# analog_sensor_x8.net
KiCad netlist of a schematic drawn in EAGLE
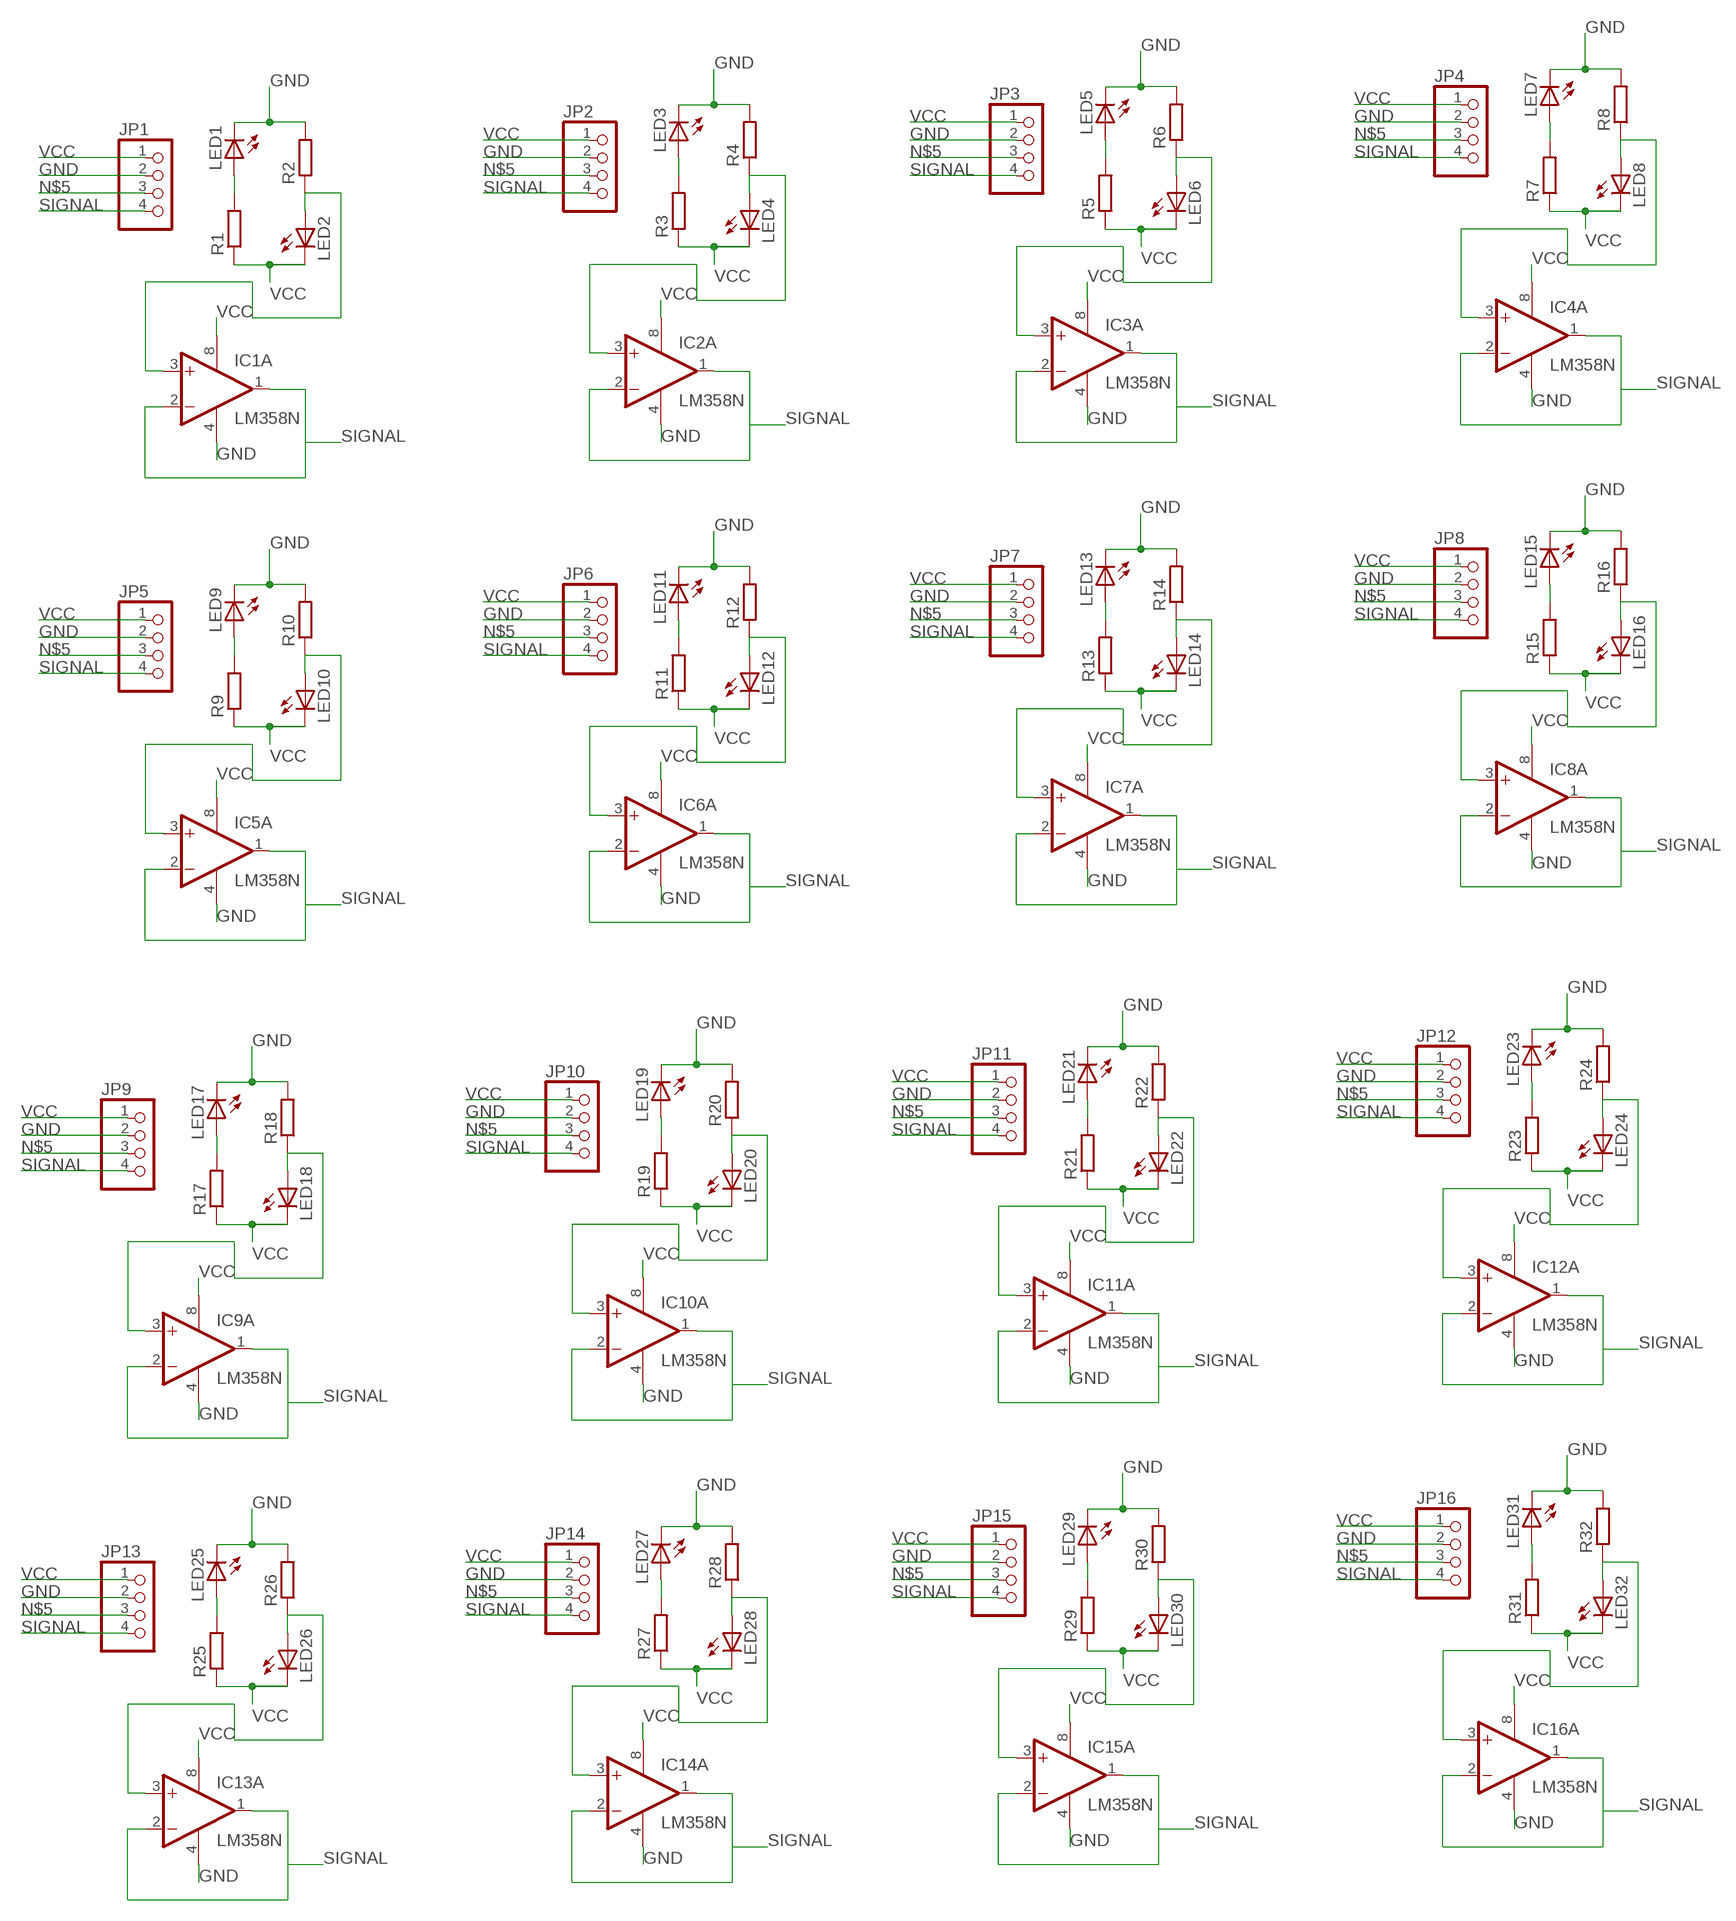
[diagram p0: schematic, sheet 1]

(export (version "E")
  (design (tool "Eeschema 10.0.6"))
  (components
    (comp (ref "IC1")
      (value "LM358N")
      (footprint "eagle-import:DIL08")
      (libsource (lib "eagle-import") (part "LM358N"))
    )
    (comp (ref "IC2")
      (value "LM358N")
      (footprint "eagle-import:DIL08")
      (libsource (lib "eagle-import") (part "LM358N"))
    )
    (comp (ref "IC3")
      (value "LM358N")
      (footprint "eagle-import:DIL08")
      (libsource (lib "eagle-import") (part "LM358N"))
    )
    (comp (ref "IC4")
      (value "LM358N")
      (footprint "eagle-import:DIL08")
      (libsource (lib "eagle-import") (part "LM358N"))
    )
    (comp (ref "IC5")
      (value "LM358N")
      (footprint "eagle-import:DIL08")
      (libsource (lib "eagle-import") (part "LM358N"))
    )
    (comp (ref "IC6")
      (value "LM358N")
      (footprint "eagle-import:DIL08")
      (libsource (lib "eagle-import") (part "LM358N"))
    )
    (comp (ref "IC7")
      (value "LM358N")
      (footprint "eagle-import:DIL08")
      (libsource (lib "eagle-import") (part "LM358N"))
    )
    (comp (ref "IC8")
      (value "LM358N")
      (footprint "eagle-import:DIL08")
      (libsource (lib "eagle-import") (part "LM358N"))
    )
    (comp (ref "IC9")
      (value "LM358N")
      (footprint "eagle-import:DIL08")
      (libsource (lib "eagle-import") (part "LM358N"))
    )
    (comp (ref "IC10")
      (value "LM358N")
      (footprint "eagle-import:DIL08")
      (libsource (lib "eagle-import") (part "LM358N"))
    )
    (comp (ref "IC11")
      (value "LM358N")
      (footprint "eagle-import:DIL08")
      (libsource (lib "eagle-import") (part "LM358N"))
    )
    (comp (ref "IC12")
      (value "LM358N")
      (footprint "eagle-import:DIL08")
      (libsource (lib "eagle-import") (part "LM358N"))
    )
    (comp (ref "IC13")
      (value "LM358N")
      (footprint "eagle-import:DIL08")
      (libsource (lib "eagle-import") (part "LM358N"))
    )
    (comp (ref "IC14")
      (value "LM358N")
      (footprint "eagle-import:DIL08")
      (libsource (lib "eagle-import") (part "LM358N"))
    )
    (comp (ref "IC15")
      (value "LM358N")
      (footprint "eagle-import:DIL08")
      (libsource (lib "eagle-import") (part "LM358N"))
    )
    (comp (ref "IC16")
      (value "LM358N")
      (footprint "eagle-import:DIL08")
      (libsource (lib "eagle-import") (part "LM358N"))
    )
    (comp (ref "JP1")
      (value "PINHD-1X4")
      (footprint "eagle-import:1X04")
      (libsource (lib "eagle-import") (part "PINHD-1X4"))
    )
    (comp (ref "JP2")
      (value "PINHD-1X4")
      (footprint "eagle-import:1X04")
      (libsource (lib "eagle-import") (part "PINHD-1X4"))
    )
    (comp (ref "JP3")
      (value "PINHD-1X4")
      (footprint "eagle-import:1X04")
      (libsource (lib "eagle-import") (part "PINHD-1X4"))
    )
    (comp (ref "JP4")
      (value "PINHD-1X4")
      (footprint "eagle-import:1X04")
      (libsource (lib "eagle-import") (part "PINHD-1X4"))
    )
    (comp (ref "JP5")
      (value "PINHD-1X4")
      (footprint "eagle-import:1X04")
      (libsource (lib "eagle-import") (part "PINHD-1X4"))
    )
    (comp (ref "JP6")
      (value "PINHD-1X4")
      (footprint "eagle-import:1X04")
      (libsource (lib "eagle-import") (part "PINHD-1X4"))
    )
    (comp (ref "JP7")
      (value "PINHD-1X4")
      (footprint "eagle-import:1X04")
      (libsource (lib "eagle-import") (part "PINHD-1X4"))
    )
    (comp (ref "JP8")
      (value "PINHD-1X4")
      (footprint "eagle-import:1X04")
      (libsource (lib "eagle-import") (part "PINHD-1X4"))
    )
    (comp (ref "JP9")
      (value "PINHD-1X4")
      (footprint "eagle-import:1X04")
      (libsource (lib "eagle-import") (part "PINHD-1X4"))
    )
    (comp (ref "JP10")
      (value "PINHD-1X4")
      (footprint "eagle-import:1X04")
      (libsource (lib "eagle-import") (part "PINHD-1X4"))
    )
    (comp (ref "JP11")
      (value "PINHD-1X4")
      (footprint "eagle-import:1X04")
      (libsource (lib "eagle-import") (part "PINHD-1X4"))
    )
    (comp (ref "JP12")
      (value "PINHD-1X4")
      (footprint "eagle-import:1X04")
      (libsource (lib "eagle-import") (part "PINHD-1X4"))
    )
    (comp (ref "JP13")
      (value "PINHD-1X4")
      (footprint "eagle-import:1X04")
      (libsource (lib "eagle-import") (part "PINHD-1X4"))
    )
    (comp (ref "JP14")
      (value "PINHD-1X4")
      (footprint "eagle-import:1X04")
      (libsource (lib "eagle-import") (part "PINHD-1X4"))
    )
    (comp (ref "JP15")
      (value "PINHD-1X4")
      (footprint "eagle-import:1X04")
      (libsource (lib "eagle-import") (part "PINHD-1X4"))
    )
    (comp (ref "JP16")
      (value "PINHD-1X4")
      (footprint "eagle-import:1X04")
      (libsource (lib "eagle-import") (part "PINHD-1X4"))
    )
    (comp (ref "LED1")
      (value "LED5MM")
      (footprint "eagle-import:LED5MM")
      (libsource (lib "eagle-import") (part "LED5MM"))
    )
    (comp (ref "LED2")
      (value "LED5MM")
      (footprint "eagle-import:LED5MM")
      (libsource (lib "eagle-import") (part "LED5MM"))
    )
    (comp (ref "LED3")
      (value "LED5MM")
      (footprint "eagle-import:LED5MM")
      (libsource (lib "eagle-import") (part "LED5MM"))
    )
    (comp (ref "LED4")
      (value "LED5MM")
      (footprint "eagle-import:LED5MM")
      (libsource (lib "eagle-import") (part "LED5MM"))
    )
    (comp (ref "LED5")
      (value "LED5MM")
      (footprint "eagle-import:LED5MM")
      (libsource (lib "eagle-import") (part "LED5MM"))
    )
    (comp (ref "LED6")
      (value "LED5MM")
      (footprint "eagle-import:LED5MM")
      (libsource (lib "eagle-import") (part "LED5MM"))
    )
    (comp (ref "LED7")
      (value "LED5MM")
      (footprint "eagle-import:LED5MM")
      (libsource (lib "eagle-import") (part "LED5MM"))
    )
    (comp (ref "LED8")
      (value "LED5MM")
      (footprint "eagle-import:LED5MM")
      (libsource (lib "eagle-import") (part "LED5MM"))
    )
    (comp (ref "LED9")
      (value "LED5MM")
      (footprint "eagle-import:LED5MM")
      (libsource (lib "eagle-import") (part "LED5MM"))
    )
    (comp (ref "LED10")
      (value "LED5MM")
      (footprint "eagle-import:LED5MM")
      (libsource (lib "eagle-import") (part "LED5MM"))
    )
    (comp (ref "LED11")
      (value "LED5MM")
      (footprint "eagle-import:LED5MM")
      (libsource (lib "eagle-import") (part "LED5MM"))
    )
    (comp (ref "LED12")
      (value "LED5MM")
      (footprint "eagle-import:LED5MM")
      (libsource (lib "eagle-import") (part "LED5MM"))
    )
    (comp (ref "LED13")
      (value "LED5MM")
      (footprint "eagle-import:LED5MM")
      (libsource (lib "eagle-import") (part "LED5MM"))
    )
    (comp (ref "LED14")
      (value "LED5MM")
      (footprint "eagle-import:LED5MM")
      (libsource (lib "eagle-import") (part "LED5MM"))
    )
    (comp (ref "LED15")
      (value "LED5MM")
      (footprint "eagle-import:LED5MM")
      (libsource (lib "eagle-import") (part "LED5MM"))
    )
    (comp (ref "LED16")
      (value "LED5MM")
      (footprint "eagle-import:LED5MM")
      (libsource (lib "eagle-import") (part "LED5MM"))
    )
    (comp (ref "LED17")
      (value "LED5MM")
      (footprint "eagle-import:LED5MM")
      (libsource (lib "eagle-import") (part "LED5MM"))
    )
    (comp (ref "LED18")
      (value "LED5MM")
      (footprint "eagle-import:LED5MM")
      (libsource (lib "eagle-import") (part "LED5MM"))
    )
    (comp (ref "LED19")
      (value "LED5MM")
      (footprint "eagle-import:LED5MM")
      (libsource (lib "eagle-import") (part "LED5MM"))
    )
    (comp (ref "LED20")
      (value "LED5MM")
      (footprint "eagle-import:LED5MM")
      (libsource (lib "eagle-import") (part "LED5MM"))
    )
    (comp (ref "LED21")
      (value "LED5MM")
      (footprint "eagle-import:LED5MM")
      (libsource (lib "eagle-import") (part "LED5MM"))
    )
    (comp (ref "LED22")
      (value "LED5MM")
      (footprint "eagle-import:LED5MM")
      (libsource (lib "eagle-import") (part "LED5MM"))
    )
    (comp (ref "LED23")
      (value "LED5MM")
      (footprint "eagle-import:LED5MM")
      (libsource (lib "eagle-import") (part "LED5MM"))
    )
    (comp (ref "LED24")
      (value "LED5MM")
      (footprint "eagle-import:LED5MM")
      (libsource (lib "eagle-import") (part "LED5MM"))
    )
    (comp (ref "LED25")
      (value "LED5MM")
      (footprint "eagle-import:LED5MM")
      (libsource (lib "eagle-import") (part "LED5MM"))
    )
    (comp (ref "LED26")
      (value "LED5MM")
      (footprint "eagle-import:LED5MM")
      (libsource (lib "eagle-import") (part "LED5MM"))
    )
    (comp (ref "LED27")
      (value "LED5MM")
      (footprint "eagle-import:LED5MM")
      (libsource (lib "eagle-import") (part "LED5MM"))
    )
    (comp (ref "LED28")
      (value "LED5MM")
      (footprint "eagle-import:LED5MM")
      (libsource (lib "eagle-import") (part "LED5MM"))
    )
    (comp (ref "LED29")
      (value "LED5MM")
      (footprint "eagle-import:LED5MM")
      (libsource (lib "eagle-import") (part "LED5MM"))
    )
    (comp (ref "LED30")
      (value "LED5MM")
      (footprint "eagle-import:LED5MM")
      (libsource (lib "eagle-import") (part "LED5MM"))
    )
    (comp (ref "LED31")
      (value "LED5MM")
      (footprint "eagle-import:LED5MM")
      (libsource (lib "eagle-import") (part "LED5MM"))
    )
    (comp (ref "LED32")
      (value "LED5MM")
      (footprint "eagle-import:LED5MM")
      (libsource (lib "eagle-import") (part "LED5MM"))
    )
    (comp (ref "R1")
      (value "R-EU_0207/10")
      (footprint "eagle-import:0207_10")
      (libsource (lib "eagle-import") (part "R-EU_0207/10"))
    )
    (comp (ref "R2")
      (value "R-EU_0207/10")
      (footprint "eagle-import:0207_10")
      (libsource (lib "eagle-import") (part "R-EU_0207/10"))
    )
    (comp (ref "R3")
      (value "R-EU_0207/10")
      (footprint "eagle-import:0207_10")
      (libsource (lib "eagle-import") (part "R-EU_0207/10"))
    )
    (comp (ref "R4")
      (value "R-EU_0207/10")
      (footprint "eagle-import:0207_10")
      (libsource (lib "eagle-import") (part "R-EU_0207/10"))
    )
    (comp (ref "R5")
      (value "R-EU_0207/10")
      (footprint "eagle-import:0207_10")
      (libsource (lib "eagle-import") (part "R-EU_0207/10"))
    )
    (comp (ref "R6")
      (value "R-EU_0207/10")
      (footprint "eagle-import:0207_10")
      (libsource (lib "eagle-import") (part "R-EU_0207/10"))
    )
    (comp (ref "R7")
      (value "R-EU_0207/10")
      (footprint "eagle-import:0207_10")
      (libsource (lib "eagle-import") (part "R-EU_0207/10"))
    )
    (comp (ref "R8")
      (value "R-EU_0207/10")
      (footprint "eagle-import:0207_10")
      (libsource (lib "eagle-import") (part "R-EU_0207/10"))
    )
    (comp (ref "R9")
      (value "R-EU_0207/10")
      (footprint "eagle-import:0207_10")
      (libsource (lib "eagle-import") (part "R-EU_0207/10"))
    )
    (comp (ref "R10")
      (value "R-EU_0207/10")
      (footprint "eagle-import:0207_10")
      (libsource (lib "eagle-import") (part "R-EU_0207/10"))
    )
    (comp (ref "R11")
      (value "R-EU_0207/10")
      (footprint "eagle-import:0207_10")
      (libsource (lib "eagle-import") (part "R-EU_0207/10"))
    )
    (comp (ref "R12")
      (value "R-EU_0207/10")
      (footprint "eagle-import:0207_10")
      (libsource (lib "eagle-import") (part "R-EU_0207/10"))
    )
    (comp (ref "R13")
      (value "R-EU_0207/10")
      (footprint "eagle-import:0207_10")
      (libsource (lib "eagle-import") (part "R-EU_0207/10"))
    )
    (comp (ref "R14")
      (value "R-EU_0207/10")
      (footprint "eagle-import:0207_10")
      (libsource (lib "eagle-import") (part "R-EU_0207/10"))
    )
    (comp (ref "R15")
      (value "R-EU_0207/10")
      (footprint "eagle-import:0207_10")
      (libsource (lib "eagle-import") (part "R-EU_0207/10"))
    )
    (comp (ref "R16")
      (value "R-EU_0207/10")
      (footprint "eagle-import:0207_10")
      (libsource (lib "eagle-import") (part "R-EU_0207/10"))
    )
    (comp (ref "R17")
      (value "R-EU_0207/10")
      (footprint "eagle-import:0207_10")
      (libsource (lib "eagle-import") (part "R-EU_0207/10"))
    )
    (comp (ref "R18")
      (value "R-EU_0207/10")
      (footprint "eagle-import:0207_10")
      (libsource (lib "eagle-import") (part "R-EU_0207/10"))
    )
    (comp (ref "R19")
      (value "R-EU_0207/10")
      (footprint "eagle-import:0207_10")
      (libsource (lib "eagle-import") (part "R-EU_0207/10"))
    )
    (comp (ref "R20")
      (value "R-EU_0207/10")
      (footprint "eagle-import:0207_10")
      (libsource (lib "eagle-import") (part "R-EU_0207/10"))
    )
    (comp (ref "R21")
      (value "R-EU_0207/10")
      (footprint "eagle-import:0207_10")
      (libsource (lib "eagle-import") (part "R-EU_0207/10"))
    )
    (comp (ref "R22")
      (value "R-EU_0207/10")
      (footprint "eagle-import:0207_10")
      (libsource (lib "eagle-import") (part "R-EU_0207/10"))
    )
    (comp (ref "R23")
      (value "R-EU_0207/10")
      (footprint "eagle-import:0207_10")
      (libsource (lib "eagle-import") (part "R-EU_0207/10"))
    )
    (comp (ref "R24")
      (value "R-EU_0207/10")
      (footprint "eagle-import:0207_10")
      (libsource (lib "eagle-import") (part "R-EU_0207/10"))
    )
    (comp (ref "R25")
      (value "R-EU_0207/10")
      (footprint "eagle-import:0207_10")
      (libsource (lib "eagle-import") (part "R-EU_0207/10"))
    )
    (comp (ref "R26")
      (value "R-EU_0207/10")
      (footprint "eagle-import:0207_10")
      (libsource (lib "eagle-import") (part "R-EU_0207/10"))
    )
    (comp (ref "R27")
      (value "R-EU_0207/10")
      (footprint "eagle-import:0207_10")
      (libsource (lib "eagle-import") (part "R-EU_0207/10"))
    )
    (comp (ref "R28")
      (value "R-EU_0207/10")
      (footprint "eagle-import:0207_10")
      (libsource (lib "eagle-import") (part "R-EU_0207/10"))
    )
    (comp (ref "R29")
      (value "R-EU_0207/10")
      (footprint "eagle-import:0207_10")
      (libsource (lib "eagle-import") (part "R-EU_0207/10"))
    )
    (comp (ref "R30")
      (value "R-EU_0207/10")
      (footprint "eagle-import:0207_10")
      (libsource (lib "eagle-import") (part "R-EU_0207/10"))
    )
    (comp (ref "R31")
      (value "R-EU_0207/10")
      (footprint "eagle-import:0207_10")
      (libsource (lib "eagle-import") (part "R-EU_0207/10"))
    )
    (comp (ref "R32")
      (value "R-EU_0207/10")
      (footprint "eagle-import:0207_10")
      (libsource (lib "eagle-import") (part "R-EU_0207/10"))
    )
  )
  (nets
    (net (code "1") (name "/GND") (class "Default")
      (node (ref "IC1") (pin "4") (pinfunction "V-_4") (pintype "power_in"))
      (node (ref "IC10") (pin "4") (pinfunction "V-_4") (pintype "power_in"))
      (node (ref "IC11") (pin "4") (pinfunction "V-_4") (pintype "power_in"))
      (node (ref "IC12") (pin "4") (pinfunction "V-_4") (pintype "power_in"))
      (node (ref "IC13") (pin "4") (pinfunction "V-_4") (pintype "power_in"))
      (node (ref "IC14") (pin "4") (pinfunction "V-_4") (pintype "power_in"))
      (node (ref "IC15") (pin "4") (pinfunction "V-_4") (pintype "power_in"))
      (node (ref "IC16") (pin "4") (pinfunction "V-_4") (pintype "power_in"))
      (node (ref "IC2") (pin "4") (pinfunction "V-_4") (pintype "power_in"))
      (node (ref "IC3") (pin "4") (pinfunction "V-_4") (pintype "power_in"))
      (node (ref "IC4") (pin "4") (pinfunction "V-_4") (pintype "power_in"))
      (node (ref "IC5") (pin "4") (pinfunction "V-_4") (pintype "power_in"))
      (node (ref "IC6") (pin "4") (pinfunction "V-_4") (pintype "power_in"))
      (node (ref "IC7") (pin "4") (pinfunction "V-_4") (pintype "power_in"))
      (node (ref "IC8") (pin "4") (pinfunction "V-_4") (pintype "power_in"))
      (node (ref "IC9") (pin "4") (pinfunction "V-_4") (pintype "power_in"))
      (node (ref "JP1") (pin "2") (pinfunction "2_2") (pintype "passive"))
      (node (ref "JP10") (pin "2") (pinfunction "2_2") (pintype "passive"))
      (node (ref "JP11") (pin "2") (pinfunction "2_2") (pintype "passive"))
      (node (ref "JP12") (pin "2") (pinfunction "2_2") (pintype "passive"))
      (node (ref "JP13") (pin "2") (pinfunction "2_2") (pintype "passive"))
      (node (ref "JP14") (pin "2") (pinfunction "2_2") (pintype "passive"))
      (node (ref "JP15") (pin "2") (pinfunction "2_2") (pintype "passive"))
      (node (ref "JP16") (pin "2") (pinfunction "2_2") (pintype "passive"))
      (node (ref "JP2") (pin "2") (pinfunction "2_2") (pintype "passive"))
      (node (ref "JP3") (pin "2") (pinfunction "2_2") (pintype "passive"))
      (node (ref "JP4") (pin "2") (pinfunction "2_2") (pintype "passive"))
      (node (ref "JP5") (pin "2") (pinfunction "2_2") (pintype "passive"))
      (node (ref "JP6") (pin "2") (pinfunction "2_2") (pintype "passive"))
      (node (ref "JP7") (pin "2") (pinfunction "2_2") (pintype "passive"))
      (node (ref "JP8") (pin "2") (pinfunction "2_2") (pintype "passive"))
      (node (ref "JP9") (pin "2") (pinfunction "2_2") (pintype "passive"))
      (node (ref "LED1") (pin "K") (pinfunction "C_K") (pintype "passive"))
      (node (ref "LED11") (pin "K") (pinfunction "C_K") (pintype "passive"))
      (node (ref "LED13") (pin "K") (pinfunction "C_K") (pintype "passive"))
      (node (ref "LED15") (pin "K") (pinfunction "C_K") (pintype "passive"))
      (node (ref "LED17") (pin "K") (pinfunction "C_K") (pintype "passive"))
      (node (ref "LED19") (pin "K") (pinfunction "C_K") (pintype "passive"))
      (node (ref "LED21") (pin "K") (pinfunction "C_K") (pintype "passive"))
      (node (ref "LED23") (pin "K") (pinfunction "C_K") (pintype "passive"))
      (node (ref "LED25") (pin "K") (pinfunction "C_K") (pintype "passive"))
      (node (ref "LED27") (pin "K") (pinfunction "C_K") (pintype "passive"))
      (node (ref "LED29") (pin "K") (pinfunction "C_K") (pintype "passive"))
      (node (ref "LED3") (pin "K") (pinfunction "C_K") (pintype "passive"))
      (node (ref "LED31") (pin "K") (pinfunction "C_K") (pintype "passive"))
      (node (ref "LED5") (pin "K") (pinfunction "C_K") (pintype "passive"))
      (node (ref "LED7") (pin "K") (pinfunction "C_K") (pintype "passive"))
      (node (ref "LED9") (pin "K") (pinfunction "C_K") (pintype "passive"))
      (node (ref "R10") (pin "2") (pinfunction "2_2") (pintype "passive"))
      (node (ref "R12") (pin "2") (pinfunction "2_2") (pintype "passive"))
      (node (ref "R14") (pin "2") (pinfunction "2_2") (pintype "passive"))
      (node (ref "R16") (pin "2") (pinfunction "2_2") (pintype "passive"))
      (node (ref "R18") (pin "2") (pinfunction "2_2") (pintype "passive"))
      (node (ref "R2") (pin "2") (pinfunction "2_2") (pintype "passive"))
      (node (ref "R20") (pin "2") (pinfunction "2_2") (pintype "passive"))
      (node (ref "R22") (pin "2") (pinfunction "2_2") (pintype "passive"))
      (node (ref "R24") (pin "2") (pinfunction "2_2") (pintype "passive"))
      (node (ref "R26") (pin "2") (pinfunction "2_2") (pintype "passive"))
      (node (ref "R28") (pin "2") (pinfunction "2_2") (pintype "passive"))
      (node (ref "R30") (pin "2") (pinfunction "2_2") (pintype "passive"))
      (node (ref "R32") (pin "2") (pinfunction "2_2") (pintype "passive"))
      (node (ref "R4") (pin "2") (pinfunction "2_2") (pintype "passive"))
      (node (ref "R6") (pin "2") (pinfunction "2_2") (pintype "passive"))
      (node (ref "R8") (pin "2") (pinfunction "2_2") (pintype "passive"))
    )
    (net (code "2") (name "/N$5") (class "Default")
      (node (ref "JP1") (pin "3") (pinfunction "3_3") (pintype "passive"))
      (node (ref "JP10") (pin "3") (pinfunction "3_3") (pintype "passive"))
      (node (ref "JP11") (pin "3") (pinfunction "3_3") (pintype "passive"))
      (node (ref "JP12") (pin "3") (pinfunction "3_3") (pintype "passive"))
      (node (ref "JP13") (pin "3") (pinfunction "3_3") (pintype "passive"))
      (node (ref "JP14") (pin "3") (pinfunction "3_3") (pintype "passive"))
      (node (ref "JP15") (pin "3") (pinfunction "3_3") (pintype "passive"))
      (node (ref "JP16") (pin "3") (pinfunction "3_3") (pintype "passive"))
      (node (ref "JP2") (pin "3") (pinfunction "3_3") (pintype "passive"))
      (node (ref "JP3") (pin "3") (pinfunction "3_3") (pintype "passive"))
      (node (ref "JP4") (pin "3") (pinfunction "3_3") (pintype "passive"))
      (node (ref "JP5") (pin "3") (pinfunction "3_3") (pintype "passive"))
      (node (ref "JP6") (pin "3") (pinfunction "3_3") (pintype "passive"))
      (node (ref "JP7") (pin "3") (pinfunction "3_3") (pintype "passive"))
      (node (ref "JP8") (pin "3") (pinfunction "3_3") (pintype "passive"))
      (node (ref "JP9") (pin "3") (pinfunction "3_3") (pintype "passive"))
    )
    (net (code "3") (name "/SIGNAL") (class "Default")
      (node (ref "IC1") (pin "1") (pinfunction "OUT_1") (pintype "output"))
      (node (ref "IC1") (pin "2") (pinfunction "-IN_2") (pintype "input"))
      (node (ref "IC10") (pin "1") (pinfunction "OUT_1") (pintype "output"))
      (node (ref "IC10") (pin "2") (pinfunction "-IN_2") (pintype "input"))
      (node (ref "IC11") (pin "1") (pinfunction "OUT_1") (pintype "output"))
      (node (ref "IC11") (pin "2") (pinfunction "-IN_2") (pintype "input"))
      (node (ref "IC12") (pin "1") (pinfunction "OUT_1") (pintype "output"))
      (node (ref "IC12") (pin "2") (pinfunction "-IN_2") (pintype "input"))
      (node (ref "IC13") (pin "1") (pinfunction "OUT_1") (pintype "output"))
      (node (ref "IC13") (pin "2") (pinfunction "-IN_2") (pintype "input"))
      (node (ref "IC14") (pin "1") (pinfunction "OUT_1") (pintype "output"))
      (node (ref "IC14") (pin "2") (pinfunction "-IN_2") (pintype "input"))
      (node (ref "IC15") (pin "1") (pinfunction "OUT_1") (pintype "output"))
      (node (ref "IC15") (pin "2") (pinfunction "-IN_2") (pintype "input"))
      (node (ref "IC16") (pin "1") (pinfunction "OUT_1") (pintype "output"))
      (node (ref "IC16") (pin "2") (pinfunction "-IN_2") (pintype "input"))
      (node (ref "IC2") (pin "1") (pinfunction "OUT_1") (pintype "output"))
      (node (ref "IC2") (pin "2") (pinfunction "-IN_2") (pintype "input"))
      (node (ref "IC3") (pin "1") (pinfunction "OUT_1") (pintype "output"))
      (node (ref "IC3") (pin "2") (pinfunction "-IN_2") (pintype "input"))
      (node (ref "IC4") (pin "1") (pinfunction "OUT_1") (pintype "output"))
      (node (ref "IC4") (pin "2") (pinfunction "-IN_2") (pintype "input"))
      (node (ref "IC5") (pin "1") (pinfunction "OUT_1") (pintype "output"))
      (node (ref "IC5") (pin "2") (pinfunction "-IN_2") (pintype "input"))
      (node (ref "IC6") (pin "1") (pinfunction "OUT_1") (pintype "output"))
      (node (ref "IC6") (pin "2") (pinfunction "-IN_2") (pintype "input"))
      (node (ref "IC7") (pin "1") (pinfunction "OUT_1") (pintype "output"))
      (node (ref "IC7") (pin "2") (pinfunction "-IN_2") (pintype "input"))
      (node (ref "IC8") (pin "1") (pinfunction "OUT_1") (pintype "output"))
      (node (ref "IC8") (pin "2") (pinfunction "-IN_2") (pintype "input"))
      (node (ref "IC9") (pin "1") (pinfunction "OUT_1") (pintype "output"))
      (node (ref "IC9") (pin "2") (pinfunction "-IN_2") (pintype "input"))
      (node (ref "JP1") (pin "4") (pinfunction "4_4") (pintype "passive"))
      (node (ref "JP10") (pin "4") (pinfunction "4_4") (pintype "passive"))
      (node (ref "JP11") (pin "4") (pinfunction "4_4") (pintype "passive"))
      (node (ref "JP12") (pin "4") (pinfunction "4_4") (pintype "passive"))
      (node (ref "JP13") (pin "4") (pinfunction "4_4") (pintype "passive"))
      (node (ref "JP14") (pin "4") (pinfunction "4_4") (pintype "passive"))
      (node (ref "JP15") (pin "4") (pinfunction "4_4") (pintype "passive"))
      (node (ref "JP16") (pin "4") (pinfunction "4_4") (pintype "passive"))
      (node (ref "JP2") (pin "4") (pinfunction "4_4") (pintype "passive"))
      (node (ref "JP3") (pin "4") (pinfunction "4_4") (pintype "passive"))
      (node (ref "JP4") (pin "4") (pinfunction "4_4") (pintype "passive"))
      (node (ref "JP5") (pin "4") (pinfunction "4_4") (pintype "passive"))
      (node (ref "JP6") (pin "4") (pinfunction "4_4") (pintype "passive"))
      (node (ref "JP7") (pin "4") (pinfunction "4_4") (pintype "passive"))
      (node (ref "JP8") (pin "4") (pinfunction "4_4") (pintype "passive"))
      (node (ref "JP9") (pin "4") (pinfunction "4_4") (pintype "passive"))
    )
    (net (code "4") (name "/VCC") (class "Default")
      (node (ref "IC1") (pin "8") (pinfunction "V+_8") (pintype "power_in"))
      (node (ref "IC10") (pin "8") (pinfunction "V+_8") (pintype "power_in"))
      (node (ref "IC11") (pin "8") (pinfunction "V+_8") (pintype "power_in"))
      (node (ref "IC12") (pin "8") (pinfunction "V+_8") (pintype "power_in"))
      (node (ref "IC13") (pin "8") (pinfunction "V+_8") (pintype "power_in"))
      (node (ref "IC14") (pin "8") (pinfunction "V+_8") (pintype "power_in"))
      (node (ref "IC15") (pin "8") (pinfunction "V+_8") (pintype "power_in"))
      (node (ref "IC16") (pin "8") (pinfunction "V+_8") (pintype "power_in"))
      (node (ref "IC2") (pin "8") (pinfunction "V+_8") (pintype "power_in"))
      (node (ref "IC3") (pin "8") (pinfunction "V+_8") (pintype "power_in"))
      (node (ref "IC4") (pin "8") (pinfunction "V+_8") (pintype "power_in"))
      (node (ref "IC5") (pin "8") (pinfunction "V+_8") (pintype "power_in"))
      (node (ref "IC6") (pin "8") (pinfunction "V+_8") (pintype "power_in"))
      (node (ref "IC7") (pin "8") (pinfunction "V+_8") (pintype "power_in"))
      (node (ref "IC8") (pin "8") (pinfunction "V+_8") (pintype "power_in"))
      (node (ref "IC9") (pin "8") (pinfunction "V+_8") (pintype "power_in"))
      (node (ref "JP1") (pin "1") (pinfunction "1_1") (pintype "passive"))
      (node (ref "JP10") (pin "1") (pinfunction "1_1") (pintype "passive"))
      (node (ref "JP11") (pin "1") (pinfunction "1_1") (pintype "passive"))
      (node (ref "JP12") (pin "1") (pinfunction "1_1") (pintype "passive"))
      (node (ref "JP13") (pin "1") (pinfunction "1_1") (pintype "passive"))
      (node (ref "JP14") (pin "1") (pinfunction "1_1") (pintype "passive"))
      (node (ref "JP15") (pin "1") (pinfunction "1_1") (pintype "passive"))
      (node (ref "JP16") (pin "1") (pinfunction "1_1") (pintype "passive"))
      (node (ref "JP2") (pin "1") (pinfunction "1_1") (pintype "passive"))
      (node (ref "JP3") (pin "1") (pinfunction "1_1") (pintype "passive"))
      (node (ref "JP4") (pin "1") (pinfunction "1_1") (pintype "passive"))
      (node (ref "JP5") (pin "1") (pinfunction "1_1") (pintype "passive"))
      (node (ref "JP6") (pin "1") (pinfunction "1_1") (pintype "passive"))
      (node (ref "JP7") (pin "1") (pinfunction "1_1") (pintype "passive"))
      (node (ref "JP8") (pin "1") (pinfunction "1_1") (pintype "passive"))
      (node (ref "JP9") (pin "1") (pinfunction "1_1") (pintype "passive"))
      (node (ref "LED10") (pin "K") (pinfunction "C_K") (pintype "passive"))
      (node (ref "LED12") (pin "K") (pinfunction "C_K") (pintype "passive"))
      (node (ref "LED14") (pin "K") (pinfunction "C_K") (pintype "passive"))
      (node (ref "LED16") (pin "K") (pinfunction "C_K") (pintype "passive"))
      (node (ref "LED18") (pin "K") (pinfunction "C_K") (pintype "passive"))
      (node (ref "LED2") (pin "K") (pinfunction "C_K") (pintype "passive"))
      (node (ref "LED20") (pin "K") (pinfunction "C_K") (pintype "passive"))
      (node (ref "LED22") (pin "K") (pinfunction "C_K") (pintype "passive"))
      (node (ref "LED24") (pin "K") (pinfunction "C_K") (pintype "passive"))
      (node (ref "LED26") (pin "K") (pinfunction "C_K") (pintype "passive"))
      (node (ref "LED28") (pin "K") (pinfunction "C_K") (pintype "passive"))
      (node (ref "LED30") (pin "K") (pinfunction "C_K") (pintype "passive"))
      (node (ref "LED32") (pin "K") (pinfunction "C_K") (pintype "passive"))
      (node (ref "LED4") (pin "K") (pinfunction "C_K") (pintype "passive"))
      (node (ref "LED6") (pin "K") (pinfunction "C_K") (pintype "passive"))
      (node (ref "LED8") (pin "K") (pinfunction "C_K") (pintype "passive"))
      (node (ref "R1") (pin "1") (pinfunction "1_1") (pintype "passive"))
      (node (ref "R11") (pin "1") (pinfunction "1_1") (pintype "passive"))
      (node (ref "R13") (pin "1") (pinfunction "1_1") (pintype "passive"))
      (node (ref "R15") (pin "1") (pinfunction "1_1") (pintype "passive"))
      (node (ref "R17") (pin "1") (pinfunction "1_1") (pintype "passive"))
      (node (ref "R19") (pin "1") (pinfunction "1_1") (pintype "passive"))
      (node (ref "R21") (pin "1") (pinfunction "1_1") (pintype "passive"))
      (node (ref "R23") (pin "1") (pinfunction "1_1") (pintype "passive"))
      (node (ref "R25") (pin "1") (pinfunction "1_1") (pintype "passive"))
      (node (ref "R27") (pin "1") (pinfunction "1_1") (pintype "passive"))
      (node (ref "R29") (pin "1") (pinfunction "1_1") (pintype "passive"))
      (node (ref "R3") (pin "1") (pinfunction "1_1") (pintype "passive"))
      (node (ref "R31") (pin "1") (pinfunction "1_1") (pintype "passive"))
      (node (ref "R5") (pin "1") (pinfunction "1_1") (pintype "passive"))
      (node (ref "R7") (pin "1") (pinfunction "1_1") (pintype "passive"))
      (node (ref "R9") (pin "1") (pinfunction "1_1") (pintype "passive"))
    )
    (net (code "5") (name "Net-(IC1A-+IN)") (class "Default")
      (node (ref "IC1") (pin "3") (pinfunction "+IN_3") (pintype "input"))
      (node (ref "LED2") (pin "A") (pinfunction "A_A") (pintype "passive"))
      (node (ref "R2") (pin "1") (pinfunction "1_1") (pintype "passive"))
    )
    (net (code "6") (name "Net-(IC2A-+IN)") (class "Default")
      (node (ref "IC2") (pin "3") (pinfunction "+IN_3") (pintype "input"))
      (node (ref "LED4") (pin "A") (pinfunction "A_A") (pintype "passive"))
      (node (ref "R4") (pin "1") (pinfunction "1_1") (pintype "passive"))
    )
    (net (code "7") (name "Net-(IC3A-+IN)") (class "Default")
      (node (ref "IC3") (pin "3") (pinfunction "+IN_3") (pintype "input"))
      (node (ref "LED6") (pin "A") (pinfunction "A_A") (pintype "passive"))
      (node (ref "R6") (pin "1") (pinfunction "1_1") (pintype "passive"))
    )
    (net (code "8") (name "Net-(IC4A-+IN)") (class "Default")
      (node (ref "IC4") (pin "3") (pinfunction "+IN_3") (pintype "input"))
      (node (ref "LED8") (pin "A") (pinfunction "A_A") (pintype "passive"))
      (node (ref "R8") (pin "1") (pinfunction "1_1") (pintype "passive"))
    )
    (net (code "9") (name "Net-(IC5A-+IN)") (class "Default")
      (node (ref "IC5") (pin "3") (pinfunction "+IN_3") (pintype "input"))
      (node (ref "LED10") (pin "A") (pinfunction "A_A") (pintype "passive"))
      (node (ref "R10") (pin "1") (pinfunction "1_1") (pintype "passive"))
    )
    (net (code "10") (name "Net-(IC6A-+IN)") (class "Default")
      (node (ref "IC6") (pin "3") (pinfunction "+IN_3") (pintype "input"))
      (node (ref "LED12") (pin "A") (pinfunction "A_A") (pintype "passive"))
      (node (ref "R12") (pin "1") (pinfunction "1_1") (pintype "passive"))
    )
    (net (code "11") (name "Net-(IC7A-+IN)") (class "Default")
      (node (ref "IC7") (pin "3") (pinfunction "+IN_3") (pintype "input"))
      (node (ref "LED14") (pin "A") (pinfunction "A_A") (pintype "passive"))
      (node (ref "R14") (pin "1") (pinfunction "1_1") (pintype "passive"))
    )
    (net (code "12") (name "Net-(IC8A-+IN)") (class "Default")
      (node (ref "IC8") (pin "3") (pinfunction "+IN_3") (pintype "input"))
      (node (ref "LED16") (pin "A") (pinfunction "A_A") (pintype "passive"))
      (node (ref "R16") (pin "1") (pinfunction "1_1") (pintype "passive"))
    )
    (net (code "13") (name "Net-(IC9A-+IN)") (class "Default")
      (node (ref "IC9") (pin "3") (pinfunction "+IN_3") (pintype "input"))
      (node (ref "LED18") (pin "A") (pinfunction "A_A") (pintype "passive"))
      (node (ref "R18") (pin "1") (pinfunction "1_1") (pintype "passive"))
    )
    (net (code "14") (name "Net-(IC10A-+IN)") (class "Default")
      (node (ref "IC10") (pin "3") (pinfunction "+IN_3") (pintype "input"))
      (node (ref "LED20") (pin "A") (pinfunction "A_A") (pintype "passive"))
      (node (ref "R20") (pin "1") (pinfunction "1_1") (pintype "passive"))
    )
    (net (code "15") (name "Net-(IC11A-+IN)") (class "Default")
      (node (ref "IC11") (pin "3") (pinfunction "+IN_3") (pintype "input"))
      (node (ref "LED22") (pin "A") (pinfunction "A_A") (pintype "passive"))
      (node (ref "R22") (pin "1") (pinfunction "1_1") (pintype "passive"))
    )
    (net (code "16") (name "Net-(IC12A-+IN)") (class "Default")
      (node (ref "IC12") (pin "3") (pinfunction "+IN_3") (pintype "input"))
      (node (ref "LED24") (pin "A") (pinfunction "A_A") (pintype "passive"))
      (node (ref "R24") (pin "1") (pinfunction "1_1") (pintype "passive"))
    )
    (net (code "17") (name "Net-(IC13A-+IN)") (class "Default")
      (node (ref "IC13") (pin "3") (pinfunction "+IN_3") (pintype "input"))
      (node (ref "LED26") (pin "A") (pinfunction "A_A") (pintype "passive"))
      (node (ref "R26") (pin "1") (pinfunction "1_1") (pintype "passive"))
    )
    (net (code "18") (name "Net-(IC14A-+IN)") (class "Default")
      (node (ref "IC14") (pin "3") (pinfunction "+IN_3") (pintype "input"))
      (node (ref "LED28") (pin "A") (pinfunction "A_A") (pintype "passive"))
      (node (ref "R28") (pin "1") (pinfunction "1_1") (pintype "passive"))
    )
    (net (code "19") (name "Net-(IC15A-+IN)") (class "Default")
      (node (ref "IC15") (pin "3") (pinfunction "+IN_3") (pintype "input"))
      (node (ref "LED30") (pin "A") (pinfunction "A_A") (pintype "passive"))
      (node (ref "R30") (pin "1") (pinfunction "1_1") (pintype "passive"))
    )
    (net (code "20") (name "Net-(IC16A-+IN)") (class "Default")
      (node (ref "IC16") (pin "3") (pinfunction "+IN_3") (pintype "input"))
      (node (ref "LED32") (pin "A") (pinfunction "A_A") (pintype "passive"))
      (node (ref "R32") (pin "1") (pinfunction "1_1") (pintype "passive"))
    )
    (net (code "21") (name "Net-(LED1-PadA)") (class "Default")
      (node (ref "LED1") (pin "A") (pinfunction "A_A") (pintype "passive"))
      (node (ref "R1") (pin "2") (pinfunction "2_2") (pintype "passive"))
    )
    (net (code "22") (name "Net-(LED3-PadA)") (class "Default")
      (node (ref "LED3") (pin "A") (pinfunction "A_A") (pintype "passive"))
      (node (ref "R3") (pin "2") (pinfunction "2_2") (pintype "passive"))
    )
    (net (code "23") (name "Net-(LED5-PadA)") (class "Default")
      (node (ref "LED5") (pin "A") (pinfunction "A_A") (pintype "passive"))
      (node (ref "R5") (pin "2") (pinfunction "2_2") (pintype "passive"))
    )
    (net (code "24") (name "Net-(LED7-PadA)") (class "Default")
      (node (ref "LED7") (pin "A") (pinfunction "A_A") (pintype "passive"))
      (node (ref "R7") (pin "2") (pinfunction "2_2") (pintype "passive"))
    )
    (net (code "25") (name "Net-(LED9-PadA)") (class "Default")
      (node (ref "LED9") (pin "A") (pinfunction "A_A") (pintype "passive"))
      (node (ref "R9") (pin "2") (pinfunction "2_2") (pintype "passive"))
    )
    (net (code "26") (name "Net-(LED11-PadA)") (class "Default")
      (node (ref "LED11") (pin "A") (pinfunction "A_A") (pintype "passive"))
      (node (ref "R11") (pin "2") (pinfunction "2_2") (pintype "passive"))
    )
    (net (code "27") (name "Net-(LED13-PadA)") (class "Default")
      (node (ref "LED13") (pin "A") (pinfunction "A_A") (pintype "passive"))
      (node (ref "R13") (pin "2") (pinfunction "2_2") (pintype "passive"))
    )
    (net (code "28") (name "Net-(LED15-PadA)") (class "Default")
      (node (ref "LED15") (pin "A") (pinfunction "A_A") (pintype "passive"))
      (node (ref "R15") (pin "2") (pinfunction "2_2") (pintype "passive"))
    )
    (net (code "29") (name "Net-(LED17-PadA)") (class "Default")
      (node (ref "LED17") (pin "A") (pinfunction "A_A") (pintype "passive"))
      (node (ref "R17") (pin "2") (pinfunction "2_2") (pintype "passive"))
    )
    (net (code "30") (name "Net-(LED19-PadA)") (class "Default")
      (node (ref "LED19") (pin "A") (pinfunction "A_A") (pintype "passive"))
      (node (ref "R19") (pin "2") (pinfunction "2_2") (pintype "passive"))
    )
    (net (code "31") (name "Net-(LED21-PadA)") (class "Default")
      (node (ref "LED21") (pin "A") (pinfunction "A_A") (pintype "passive"))
      (node (ref "R21") (pin "2") (pinfunction "2_2") (pintype "passive"))
    )
    (net (code "32") (name "Net-(LED23-PadA)") (class "Default")
      (node (ref "LED23") (pin "A") (pinfunction "A_A") (pintype "passive"))
      (node (ref "R23") (pin "2") (pinfunction "2_2") (pintype "passive"))
    )
    (net (code "33") (name "Net-(LED25-PadA)") (class "Default")
      (node (ref "LED25") (pin "A") (pinfunction "A_A") (pintype "passive"))
      (node (ref "R25") (pin "2") (pinfunction "2_2") (pintype "passive"))
    )
    (net (code "34") (name "Net-(LED27-PadA)") (class "Default")
      (node (ref "LED27") (pin "A") (pinfunction "A_A") (pintype "passive"))
      (node (ref "R27") (pin "2") (pinfunction "2_2") (pintype "passive"))
    )
    (net (code "35") (name "Net-(LED29-PadA)") (class "Default")
      (node (ref "LED29") (pin "A") (pinfunction "A_A") (pintype "passive"))
      (node (ref "R29") (pin "2") (pinfunction "2_2") (pintype "passive"))
    )
    (net (code "36") (name "Net-(LED31-PadA)") (class "Default")
      (node (ref "LED31") (pin "A") (pinfunction "A_A") (pintype "passive"))
      (node (ref "R31") (pin "2") (pinfunction "2_2") (pintype "passive"))
    )
  )
)
